# RPI-Lora-Gateway-Shield.net
KiCad netlist of a schematic drawn in EAGLE
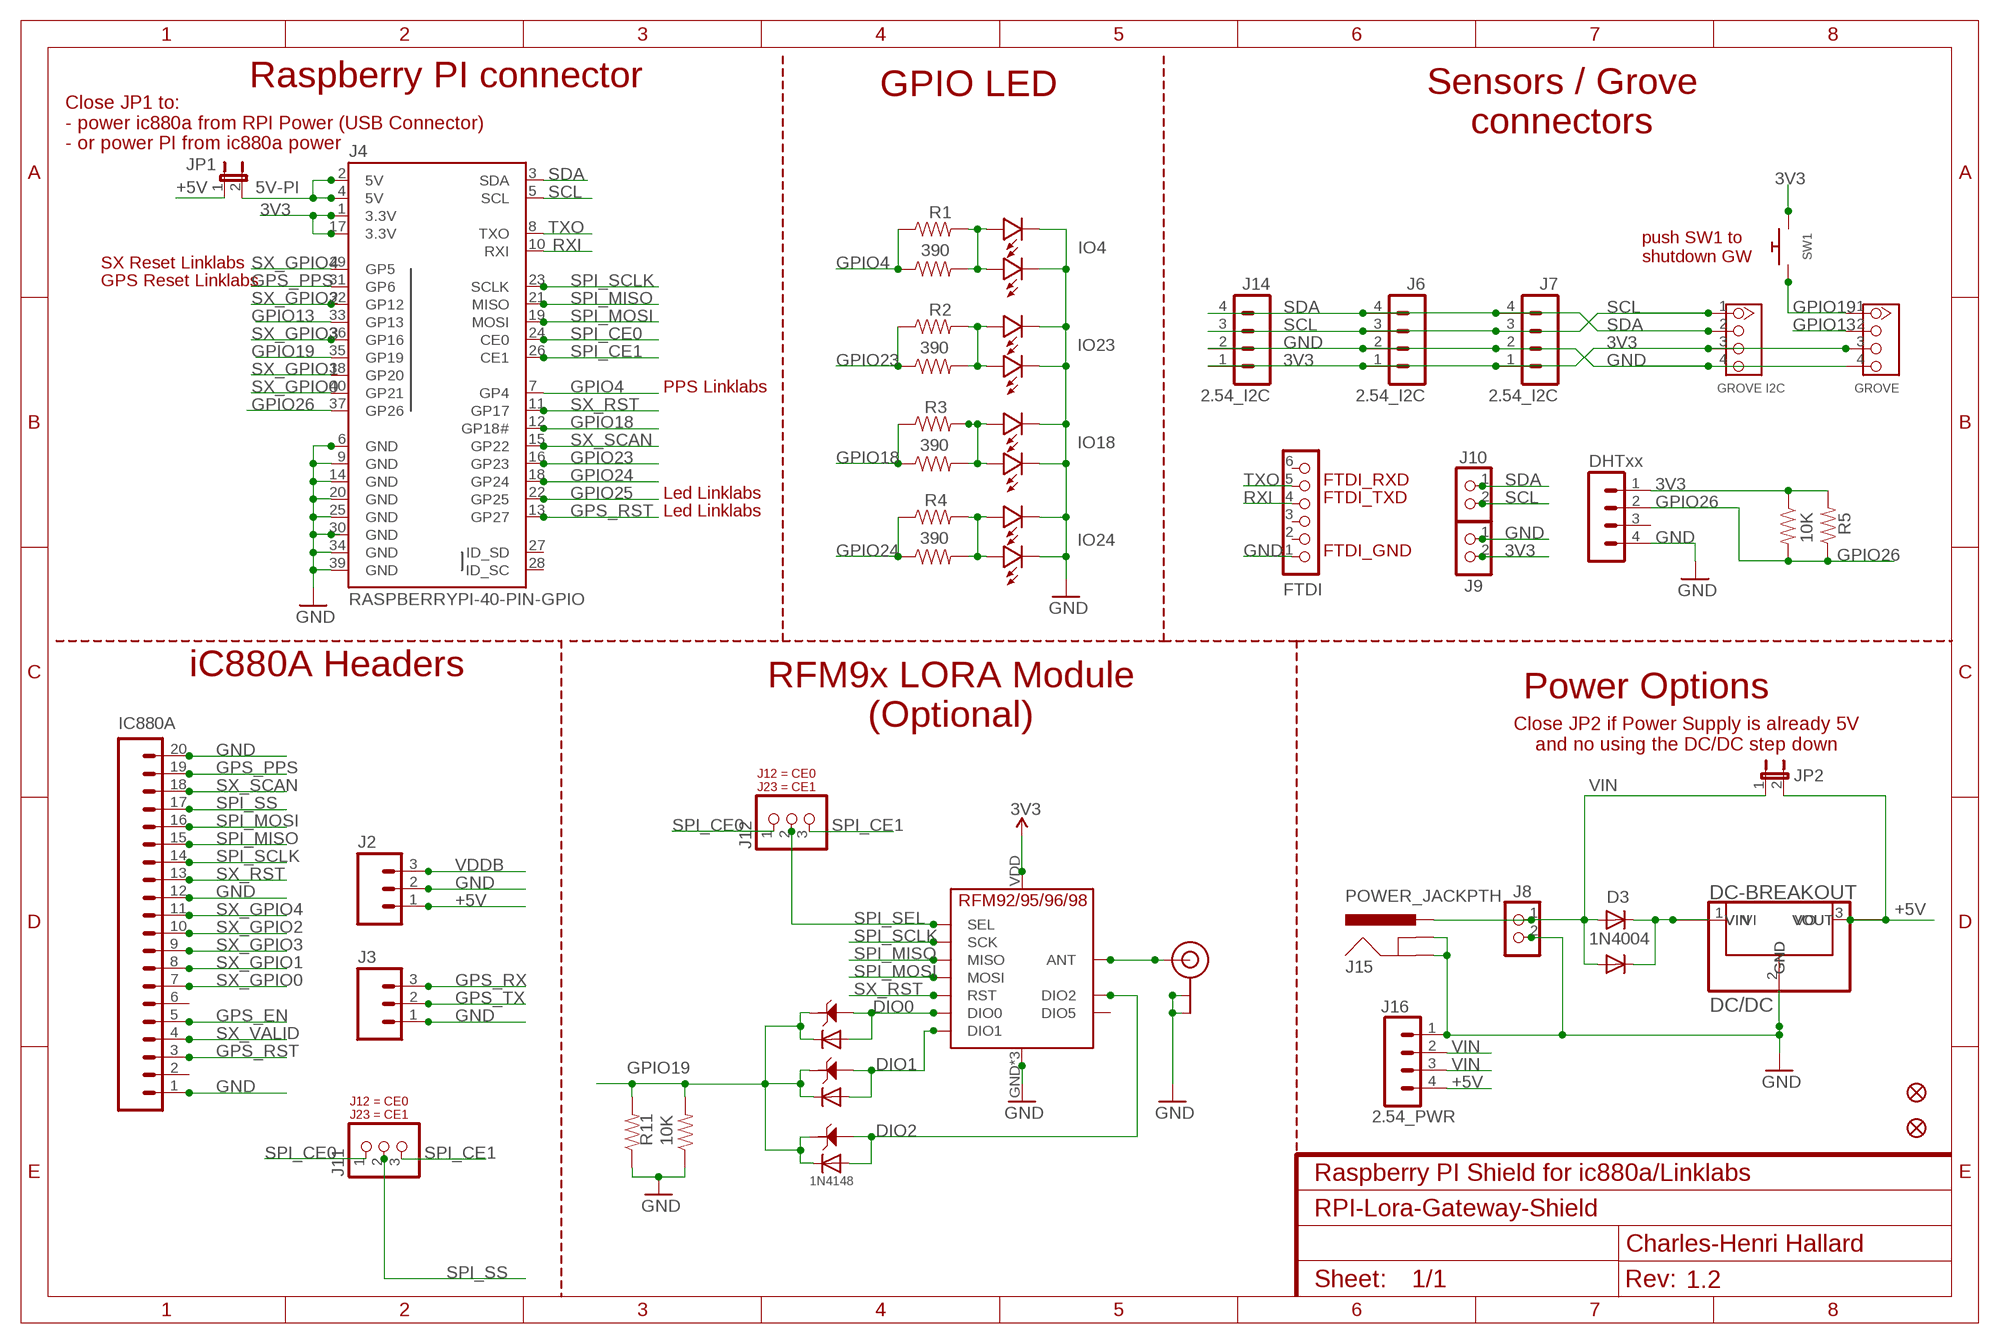
[diagram p0: schematic, sheet 1]

(export (version "E")
  (design (tool "Eeschema 10.0.6"))
  (components
    (comp (ref "D0")
      (value "1N4148")
      (footprint "eagle-import:SOD123-2.7X1.6")
      (libsource (lib "eagle-import") (part "D-ESD-2P-CESD5V0D1"))
    )
    (comp (ref "D1")
      (value "1N4148")
      (footprint "eagle-import:SOD123-2.7X1.6")
      (libsource (lib "eagle-import") (part "D-ESD-2P-CESD5V0D1"))
    )
    (comp (ref "D2")
      (value "1N4148")
      (footprint "eagle-import:SOD123-2.7X1.6")
      (libsource (lib "eagle-import") (part "D-ESD-2P-CESD5V0D1"))
    )
    (comp (ref "D3")
      (value "1N4004")
      (footprint "eagle-import:DO41-10")
      (libsource (lib "eagle-import") (part "1N4004"))
    )
    (comp (ref "D4")
      (value "1N4007")
      (footprint "eagle-import:DO-214AC")
      (libsource (lib "eagle-import") (part "DIODE-DO-214AC"))
    )
    (comp (ref "D5")
      (value "1N4148")
      (footprint "eagle-import:DO-1N4148")
      (libsource (lib "eagle-import") (part "DIODEDO-1N4148"))
    )
    (comp (ref "D6")
      (value "DIODEDO-1N4148")
      (footprint "eagle-import:DO-1N4148")
      (libsource (lib "eagle-import") (part "DIODEDO-1N4148"))
    )
    (comp (ref "D7")
      (value "DIODEDO-1N4148")
      (footprint "eagle-import:DO-1N4148")
      (libsource (lib "eagle-import") (part "DIODEDO-1N4148"))
    )
    (comp (ref "DC/DC")
      (value "DC-BREAKOUT")
      (footprint "eagle-import:DC-BREAKOUT")
      (libsource (lib "eagle-import") (part "DC-BREAKOUTSTD"))
    )
    (comp (ref "FID2")
      (value "FIDUCIAL\"\"")
      (footprint "eagle-import:FIDUCIAL_1MM")
      (libsource (lib "eagle-import") (part "FIDUCIAL{dblquote}{dblquote}"))
    )
    (comp (ref "FID3")
      (value "FIDUCIAL\"\"")
      (footprint "eagle-import:FIDUCIAL_1MM")
      (libsource (lib "eagle-import") (part "FIDUCIAL{dblquote}{dblquote}"))
    )
    (comp (ref "FTDI")
      (value "CON_HEADER_1X06-PTH")
      (footprint "eagle-import:M1X6")
      (libsource (lib "eagle-import") (part "CON_HEADER_1X06-PTH"))
    )
    (comp (ref "IC880A")
      (value "M20LOCK")
      (footprint "eagle-import:1X20_LOCK")
      (libsource (lib "eagle-import") (part "M20LOCK"))
    )
    (comp (ref "J1")
      (value "GROVE")
      (footprint "eagle-import:HW4-2.0")
      (libsource (lib "eagle-import") (part "GROVE-CONNECTOR-DIP(4P-2.0)"))
    )
    (comp (ref "J2")
      (value "M03LOCK")
      (footprint "eagle-import:1X03_LOCK")
      (libsource (lib "eagle-import") (part "M03LOCK"))
    )
    (comp (ref "J3")
      (value "M03LOCK")
      (footprint "eagle-import:1X03_LOCK")
      (libsource (lib "eagle-import") (part "M03LOCK"))
    )
    (comp (ref "J4")
      (value "RASPBERRYPI-40-PIN-GPIO")
      (footprint "eagle-import:2X20-SHROUDED")
      (libsource (lib "eagle-import") (part "RASPBERRYPI-40-PIN-GPIO"))
    )
    (comp (ref "J5")
      (value "DHTxx")
      (footprint "eagle-import:1X04_NO_LOCK")
      (libsource (lib "eagle-import") (part "CON_HEADER_1X04'NO_LOCK'"))
    )
    (comp (ref "J6")
      (value "2.54_I2C")
      (footprint "eagle-import:1X04_NO_LOCK")
      (libsource (lib "eagle-import") (part "CON_HEADER_1X04'NO_LOCK'"))
    )
    (comp (ref "J7")
      (value "2.54_I2C")
      (footprint "eagle-import:1X04_NO_LOCK")
      (libsource (lib "eagle-import") (part "CON_HEADER_1X04'NO_LOCK'"))
    )
    (comp (ref "J8")
      (value "CON_TERMINAL_BLOCK_02-5MM")
      (footprint "eagle-import:TERMINAL_BLOCK_2P_5")
      (libsource (lib "eagle-import") (part "CON_TERMINAL_BLOCK_02-5MM"))
    )
    (comp (ref "J9")
      (value "CON_TERMINAL_BLOCK_02-5MM")
      (footprint "eagle-import:TERMINAL_BLOCK_2P_5")
      (libsource (lib "eagle-import") (part "CON_TERMINAL_BLOCK_02-5MM"))
    )
    (comp (ref "J10")
      (value "CON_TERMINAL_BLOCK_02-5MM")
      (footprint "eagle-import:TERMINAL_BLOCK_2P_5")
      (libsource (lib "eagle-import") (part "CON_TERMINAL_BLOCK_02-5MM"))
    )
    (comp (ref "J11")
      (value "JUMPER_1X30805")
      (footprint "eagle-import:JP3_0805")
      (fields
        (field (name "J12") "optA")
        (field (name "J23") "optB")
        (field (name "J12_1") "CE0")
        (field (name "J23_1") "CE1")
      )
      (libsource (lib "eagle-import") (part "JUMPER_1X30805"))
    )
    (comp (ref "J12")
      (value "JUMPER_1X30805")
      (footprint "eagle-import:JP3_0805")
      (fields
        (field (name "J12") "optA")
        (field (name "J23") "optB")
        (field (name "J12_1") "CE0")
        (field (name "J23_1") "CE1")
      )
      (libsource (lib "eagle-import") (part "JUMPER_1X30805"))
    )
    (comp (ref "J13")
      (value "GROVE I2C")
      (footprint "eagle-import:HW4-2.0")
      (libsource (lib "eagle-import") (part "GROVE-CONNECTOR-DIP(4P-2.0)"))
    )
    (comp (ref "J14")
      (value "2.54_I2C")
      (footprint "eagle-import:1X04_NO_LOCK")
      (libsource (lib "eagle-import") (part "CON_HEADER_1X04'NO_LOCK'"))
    )
    (comp (ref "J15")
      (value "POWER_JACKPTH")
      (footprint "eagle-import:POWER_JACK_PTH")
      (libsource (lib "eagle-import") (part "POWER_JACKPTH"))
    )
    (comp (ref "J16")
      (value "2.54_PWR")
      (footprint "eagle-import:1X04_NO_LOCK")
      (libsource (lib "eagle-import") (part "CON_HEADER_1X04'NO_LOCK'"))
    )
    (comp (ref "JP1")
      (value "JUMPER2")
      (footprint "eagle-import:JUMPER2")
      (libsource (lib "eagle-import") (part "JUMPER2"))
    )
    (comp (ref "JP2")
      (value "JUMPER2")
      (footprint "eagle-import:JUMPER2")
      (libsource (lib "eagle-import") (part "JUMPER2"))
    )
    (comp (ref "LED1")
      (value "LED0805")
      (footprint "eagle-import:0805-LED")
      (libsource (lib "eagle-import") (part "LED0805"))
    )
    (comp (ref "LED2")
      (value "LED0805")
      (footprint "eagle-import:0805-LED")
      (libsource (lib "eagle-import") (part "LED0805"))
    )
    (comp (ref "LED3")
      (value "LED0805")
      (footprint "eagle-import:0805-LED")
      (libsource (lib "eagle-import") (part "LED0805"))
    )
    (comp (ref "LED4")
      (value "LED0805")
      (footprint "eagle-import:0805-LED")
      (libsource (lib "eagle-import") (part "LED0805"))
    )
    (comp (ref "R1")
      (value "390")
      (footprint "eagle-import:AXIAL-0.4")
      (libsource (lib "eagle-import") (part "RESISTORPTH-1/4W"))
    )
    (comp (ref "R2")
      (value "390")
      (footprint "eagle-import:AXIAL-0.4")
      (libsource (lib "eagle-import") (part "RESISTORPTH-1/4W"))
    )
    (comp (ref "R3")
      (value "390")
      (footprint "eagle-import:AXIAL-0.4")
      (libsource (lib "eagle-import") (part "RESISTORPTH-1/4W"))
    )
    (comp (ref "R4")
      (value "390")
      (footprint "eagle-import:AXIAL-0.4")
      (libsource (lib "eagle-import") (part "RESISTORPTH-1/4W"))
    )
    (comp (ref "R5")
      (value "10K")
      (footprint "eagle-import:AXIAL-0.4")
      (libsource (lib "eagle-import") (part "RESISTORPTH-1/4W"))
    )
    (comp (ref "R6")
      (value "RESISTOR0805-RES")
      (footprint "eagle-import:0805-RES")
      (libsource (lib "eagle-import") (part "RESISTOR0805-RES"))
    )
    (comp (ref "R7")
      (value "RESISTOR0805-RES")
      (footprint "eagle-import:0805-RES")
      (libsource (lib "eagle-import") (part "RESISTOR0805-RES"))
    )
    (comp (ref "R8")
      (value "RESISTOR0805-RES")
      (footprint "eagle-import:0805-RES")
      (libsource (lib "eagle-import") (part "RESISTOR0805-RES"))
    )
    (comp (ref "R9")
      (value "RESISTOR0805-RES")
      (footprint "eagle-import:0805-RES")
      (libsource (lib "eagle-import") (part "RESISTOR0805-RES"))
    )
    (comp (ref "R10")
      (value "RESISTOR0805-RES")
      (footprint "eagle-import:0805-RES")
      (libsource (lib "eagle-import") (part "RESISTOR0805-RES"))
    )
    (comp (ref "R11")
      (value "10K")
      (footprint "eagle-import:AXIAL-0.4")
      (libsource (lib "eagle-import") (part "RESISTORPTH-1/4W"))
    )
    (comp (ref "R12")
      (value "RESISTOR0805-RES")
      (footprint "eagle-import:0805-RES")
      (libsource (lib "eagle-import") (part "RESISTOR0805-RES"))
    )
    (comp (ref "SW1")
      (value "SWITCH_PUSHBUTTONEVQ-PE")
      (footprint "eagle-import:TACT_PANA-EVQ")
      (libsource (lib "eagle-import") (part "SWITCH_PUSHBUTTONEVQ-PE"))
    )
    (comp (ref "U$2")
      (value "RFM95")
      (footprint "eagle-import:RFM95")
      (libsource (lib "eagle-import") (part "RFM95"))
    )
    (comp (ref "U$3")
      (value "ANTENNA-UFL")
      (footprint "eagle-import:UFL_PAD")
      (libsource (lib "eagle-import") (part "ANTENNA-UFL"))
    )
    (comp (ref "U$4")
      (value "IO4")
      (footprint "eagle-import:LED3MM")
      (libsource (lib "eagle-import") (part "LED3MM"))
    )
    (comp (ref "U$5")
      (value "IO23")
      (footprint "eagle-import:LED3MM")
      (libsource (lib "eagle-import") (part "LED3MM"))
    )
    (comp (ref "U$6")
      (value "IO18")
      (footprint "eagle-import:LED3MM")
      (libsource (lib "eagle-import") (part "LED3MM"))
    )
    (comp (ref "U$7")
      (value "IO24")
      (footprint "eagle-import:LED3MM")
      (libsource (lib "eagle-import") (part "LED3MM"))
    )
    (comp (ref "U$8")
      (value "DC-BREAKOUTFIXED")
      (footprint "eagle-import:DC-DC-FIXED")
      (libsource (lib "eagle-import") (part "DC-BREAKOUTFIXED"))
    )
    (comp (ref "U$11")
      (value "OKI-78SR")
      (footprint "eagle-import:OKI-78SRH")
      (libsource (lib "eagle-import") (part "DCDC_OKI-78SRHORZ"))
    )
  )
  (nets
    (net (code "1") (name "/+5V") (class "Default")
      (node (ref "DC/DC") (pin "VOUT-1") (pinfunction "VOUT_VOUT-1") (pintype "output"))
      (node (ref "DC/DC") (pin "VOUT-2") (pinfunction "VOUT_VOUT-2") (pintype "output"))
      (node (ref "J16") (pin "4") (pinfunction "4_4") (pintype "passive"))
      (node (ref "J2") (pin "1") (pinfunction "1_1") (pintype "passive"))
      (node (ref "JP1") (pin "1") (pinfunction "1_1") (pintype "passive"))
      (node (ref "JP2") (pin "2") (pinfunction "2_2") (pintype "passive"))
      (node (ref "U$11") (pin "3") (pinfunction "VO_3") (pintype "bidirectional"))
      (node (ref "U$8") (pin "VOUT-1") (pinfunction "VOUT_VOUT-1") (pintype "output"))
      (node (ref "U$8") (pin "VOUT-2") (pinfunction "VOUT_VOUT-2") (pintype "output"))
    )
    (net (code "2") (name "/5V-PI") (class "Default")
      (node (ref "J4") (pin "2") (pinfunction "5V_2") (pintype "power_in"))
      (node (ref "J4") (pin "4") (pinfunction "5V_4") (pintype "power_in"))
      (node (ref "JP1") (pin "2") (pinfunction "2_2") (pintype "passive"))
    )
    (net (code "3") (name "/DIO0") (class "Default")
      (node (ref "D0") (pin "1") (pinfunction "1_1") (pintype "bidirectional"))
      (node (ref "D6") (pin "A") (pinfunction "A_A") (pintype "passive"))
      (node (ref "U$2") (pin "DIO0") (pinfunction "DIO0_DIO0") (pintype "open_collector"))
    )
    (net (code "4") (name "/DIO1") (class "Default")
      (node (ref "D1") (pin "1") (pinfunction "1_1") (pintype "bidirectional"))
      (node (ref "D7") (pin "A") (pinfunction "A_A") (pintype "passive"))
      (node (ref "U$2") (pin "DIO1") (pinfunction "DIO1_DIO1") (pintype "open_collector"))
    )
    (net (code "5") (name "/DIO2") (class "Default")
      (node (ref "D2") (pin "1") (pinfunction "1_1") (pintype "bidirectional"))
      (node (ref "D5") (pin "A") (pinfunction "A_A") (pintype "passive"))
      (node (ref "U$2") (pin "DIO2") (pinfunction "DIO2_DIO2") (pintype "open_collector"))
    )
    (net (code "6") (name "/GPIO4") (class "Default")
      (node (ref "J4") (pin "7") (pinfunction "GP4_7") (pintype "bidirectional"))
      (node (ref "R1") (pin "P$1") (pinfunction "1_P$1") (pintype "passive"))
      (node (ref "R6") (pin "1") (pinfunction "1_1") (pintype "passive"))
    )
    (net (code "7") (name "/GPIO13") (class "Default")
      (node (ref "J1") (pin "2") (pinfunction "2_2") (pintype "bidirectional"))
      (node (ref "J4") (pin "33") (pinfunction "GP13_33") (pintype "bidirectional"))
    )
    (net (code "8") (name "/GPIO18") (class "Default")
      (node (ref "J4") (pin "12") (pinfunction "GP18#_12") (pintype "bidirectional"))
      (node (ref "R3") (pin "P$1") (pinfunction "1_P$1") (pintype "passive"))
      (node (ref "R8") (pin "1") (pinfunction "1_1") (pintype "passive"))
    )
    (net (code "9") (name "/GPIO19") (class "Default")
      (node (ref "D0") (pin "2") (pinfunction "2_2") (pintype "bidirectional"))
      (node (ref "D1") (pin "2") (pinfunction "2_2") (pintype "bidirectional"))
      (node (ref "D2") (pin "2") (pinfunction "2_2") (pintype "bidirectional"))
      (node (ref "D5") (pin "C") (pinfunction "C_C") (pintype "passive"))
      (node (ref "D6") (pin "C") (pinfunction "C_C") (pintype "passive"))
      (node (ref "D7") (pin "C") (pinfunction "C_C") (pintype "passive"))
      (node (ref "J1") (pin "1") (pinfunction "1_1") (pintype "bidirectional"))
      (node (ref "J4") (pin "35") (pinfunction "GP19_35") (pintype "bidirectional"))
      (node (ref "R11") (pin "P$2") (pinfunction "2_P$2") (pintype "passive"))
      (node (ref "R12") (pin "2") (pinfunction "2_2") (pintype "passive"))
      (node (ref "SW1") (pin "P$1") (pinfunction "P$1_P$1") (pintype "passive"))
    )
    (net (code "10") (name "/GPIO23") (class "Default")
      (node (ref "J4") (pin "16") (pinfunction "GP23_16") (pintype "bidirectional"))
      (node (ref "R2") (pin "P$1") (pinfunction "1_P$1") (pintype "passive"))
      (node (ref "R7") (pin "1") (pinfunction "1_1") (pintype "passive"))
    )
    (net (code "11") (name "/GPIO24") (class "Default")
      (node (ref "J4") (pin "18") (pinfunction "GP24_18") (pintype "bidirectional"))
      (node (ref "R4") (pin "P$1") (pinfunction "1_P$1") (pintype "passive"))
      (node (ref "R9") (pin "1") (pinfunction "1_1") (pintype "passive"))
    )
    (net (code "12") (name "/GPIO25") (class "Default")
      (node (ref "J4") (pin "22") (pinfunction "GP25_22") (pintype "bidirectional"))
    )
    (net (code "13") (name "/GPIO26") (class "Default")
      (node (ref "J4") (pin "37") (pinfunction "GP26_37") (pintype "bidirectional"))
      (node (ref "J5") (pin "2") (pinfunction "2_2") (pintype "passive"))
      (node (ref "R10") (pin "1") (pinfunction "1_1") (pintype "passive"))
      (node (ref "R5") (pin "P$2") (pinfunction "2_P$2") (pintype "passive"))
    )
    (net (code "14") (name "/GPS_EN") (class "Default")
      (node (ref "IC880A") (pin "5") (pinfunction "5_5") (pintype "passive"))
    )
    (net (code "15") (name "/GPS_PPS") (class "Default")
      (node (ref "IC880A") (pin "19") (pinfunction "19_19") (pintype "passive"))
      (node (ref "J4") (pin "31") (pinfunction "GP6_31") (pintype "bidirectional"))
    )
    (net (code "16") (name "/GPS_RST") (class "Default")
      (node (ref "IC880A") (pin "3") (pinfunction "3_3") (pintype "passive"))
      (node (ref "J4") (pin "13") (pinfunction "GP27_13") (pintype "bidirectional"))
    )
    (net (code "17") (name "/GPS_RX") (class "Default")
      (node (ref "J3") (pin "3") (pinfunction "3_3") (pintype "passive"))
    )
    (net (code "18") (name "/GPS_TX") (class "Default")
      (node (ref "J3") (pin "2") (pinfunction "2_2") (pintype "passive"))
    )
    (net (code "19") (name "/RXI") (class "Default")
      (node (ref "FTDI") (pin "4") (pinfunction "4_4") (pintype "passive"))
      (node (ref "J4") (pin "10") (pinfunction "RXI_10") (pintype "input"))
    )
    (net (code "20") (name "/SCL") (class "Default")
      (node (ref "J10") (pin "2") (pinfunction "2_2") (pintype "passive"))
      (node (ref "J13") (pin "1") (pinfunction "1_1") (pintype "bidirectional"))
      (node (ref "J14") (pin "3") (pinfunction "3_3") (pintype "passive"))
      (node (ref "J4") (pin "5") (pinfunction "SCL_5") (pintype "bidirectional"))
      (node (ref "J6") (pin "3") (pinfunction "3_3") (pintype "passive"))
      (node (ref "J7") (pin "3") (pinfunction "3_3") (pintype "passive"))
    )
    (net (code "21") (name "/SDA") (class "Default")
      (node (ref "J10") (pin "1") (pinfunction "1_1") (pintype "passive"))
      (node (ref "J13") (pin "2") (pinfunction "2_2") (pintype "bidirectional"))
      (node (ref "J14") (pin "4") (pinfunction "4_4") (pintype "passive"))
      (node (ref "J4") (pin "3") (pinfunction "SDA_3") (pintype "bidirectional"))
      (node (ref "J6") (pin "4") (pinfunction "4_4") (pintype "passive"))
      (node (ref "J7") (pin "4") (pinfunction "4_4") (pintype "passive"))
    )
    (net (code "22") (name "/SPI_CE0") (class "Default")
      (node (ref "J11") (pin "1") (pinfunction "1_1") (pintype "passive"))
      (node (ref "J12") (pin "1") (pinfunction "1_1") (pintype "passive"))
      (node (ref "J4") (pin "24") (pinfunction "CE0_24") (pintype "output"))
    )
    (net (code "23") (name "/SPI_CE1") (class "Default")
      (node (ref "J11") (pin "3") (pinfunction "3_3") (pintype "passive"))
      (node (ref "J12") (pin "3") (pinfunction "3_3") (pintype "passive"))
      (node (ref "J4") (pin "26") (pinfunction "CE1_26") (pintype "output"))
    )
    (net (code "24") (name "/SPI_MISO") (class "Default")
      (node (ref "IC880A") (pin "15") (pinfunction "15_15") (pintype "passive"))
      (node (ref "J4") (pin "21") (pinfunction "MISO_21") (pintype "input"))
      (node (ref "U$2") (pin "MISO") (pinfunction "MISO_MISO") (pintype "input"))
    )
    (net (code "25") (name "/SPI_MOSI") (class "Default")
      (node (ref "IC880A") (pin "16") (pinfunction "16_16") (pintype "passive"))
      (node (ref "J4") (pin "19") (pinfunction "MOSI_19") (pintype "output"))
      (node (ref "U$2") (pin "MOSI") (pinfunction "MOSI_MOSI") (pintype "output"))
    )
    (net (code "26") (name "/SPI_SCLK") (class "Default")
      (node (ref "IC880A") (pin "14") (pinfunction "14_14") (pintype "passive"))
      (node (ref "J4") (pin "23") (pinfunction "SCLK_23") (pintype "output"))
      (node (ref "U$2") (pin "SCK") (pinfunction "SCK_SCK") (pintype "input"))
    )
    (net (code "27") (name "/SPI_SEL") (class "Default")
      (node (ref "J12") (pin "2") (pinfunction "2_2") (pintype "passive"))
      (node (ref "U$2") (pin "NSS") (pinfunction "SEL_NSS") (pintype "input"))
    )
    (net (code "28") (name "/SPI_SS") (class "Default")
      (node (ref "IC880A") (pin "17") (pinfunction "17_17") (pintype "passive"))
      (node (ref "J11") (pin "2") (pinfunction "2_2") (pintype "passive"))
    )
    (net (code "29") (name "/SX_GPIO0") (class "Default")
      (node (ref "IC880A") (pin "7") (pinfunction "7_7") (pintype "passive"))
      (node (ref "J4") (pin "40") (pinfunction "GP21_40") (pintype "bidirectional"))
    )
    (net (code "30") (name "/SX_GPIO1") (class "Default")
      (node (ref "IC880A") (pin "8") (pinfunction "8_8") (pintype "passive"))
      (node (ref "J4") (pin "38") (pinfunction "GP20_38") (pintype "bidirectional"))
    )
    (net (code "31") (name "/SX_GPIO2") (class "Default")
      (node (ref "IC880A") (pin "10") (pinfunction "10_10") (pintype "passive"))
      (node (ref "J4") (pin "32") (pinfunction "GP12_32") (pintype "bidirectional"))
    )
    (net (code "32") (name "/SX_GPIO3") (class "Default")
      (node (ref "IC880A") (pin "9") (pinfunction "9_9") (pintype "passive"))
      (node (ref "J4") (pin "36") (pinfunction "GP16_36") (pintype "bidirectional"))
    )
    (net (code "33") (name "/SX_GPIO4") (class "Default")
      (node (ref "IC880A") (pin "11") (pinfunction "11_11") (pintype "passive"))
      (node (ref "J4") (pin "29") (pinfunction "GP5_29") (pintype "bidirectional"))
    )
    (net (code "34") (name "/SX_RST") (class "Default")
      (node (ref "IC880A") (pin "13") (pinfunction "13_13") (pintype "passive"))
      (node (ref "J4") (pin "11") (pinfunction "GP17_11") (pintype "bidirectional"))
      (node (ref "U$2") (pin "RST") (pinfunction "RST_RST") (pintype "open_collector"))
    )
    (net (code "35") (name "/SX_SCAN") (class "Default")
      (node (ref "IC880A") (pin "18") (pinfunction "18_18") (pintype "passive"))
      (node (ref "J4") (pin "15") (pinfunction "GP22_15") (pintype "bidirectional"))
    )
    (net (code "36") (name "/SX_VALID") (class "Default")
      (node (ref "IC880A") (pin "4") (pinfunction "4_4") (pintype "passive"))
    )
    (net (code "37") (name "/TXO") (class "Default")
      (node (ref "FTDI") (pin "5") (pinfunction "5_5") (pintype "passive"))
      (node (ref "J4") (pin "8") (pinfunction "TXO_8") (pintype "output"))
    )
    (net (code "38") (name "/VDDB") (class "Default")
      (node (ref "J2") (pin "3") (pinfunction "3_3") (pintype "passive"))
    )
    (net (code "39") (name "/VIN") (class "Default")
      (node (ref "D3") (pin "A") (pinfunction "A_A") (pintype "passive"))
      (node (ref "D4") (pin "2") (pinfunction "A_2") (pintype "passive"))
      (node (ref "J15") (pin "PWR") (pinfunction "PWR_PWR") (pintype "bidirectional"))
      (node (ref "J16") (pin "2") (pinfunction "2_2") (pintype "passive"))
      (node (ref "J16") (pin "3") (pinfunction "3_3") (pintype "passive"))
      (node (ref "J8") (pin "1") (pinfunction "1_1") (pintype "passive"))
      (node (ref "JP2") (pin "1") (pinfunction "1_1") (pintype "passive"))
    )
    (net (code "40") (name "3V3") (class "Default")
      (node (ref "J1") (pin "3") (pinfunction "3_3") (pintype "bidirectional"))
      (node (ref "J13") (pin "3") (pinfunction "3_3") (pintype "bidirectional"))
      (node (ref "J14") (pin "1") (pinfunction "1_1") (pintype "passive"))
      (node (ref "J4") (pin "1") (pinfunction "3.3V_1") (pintype "power_in"))
      (node (ref "J4") (pin "17") (pinfunction "3.3V_17") (pintype "power_in"))
      (node (ref "J5") (pin "1") (pinfunction "1_1") (pintype "passive"))
      (node (ref "J6") (pin "1") (pinfunction "1_1") (pintype "passive"))
      (node (ref "J7") (pin "1") (pinfunction "1_1") (pintype "passive"))
      (node (ref "J9") (pin "2") (pinfunction "2_2") (pintype "passive"))
      (node (ref "R10") (pin "2") (pinfunction "2_2") (pintype "passive"))
      (node (ref "R5") (pin "P$1") (pinfunction "1_P$1") (pintype "passive"))
      (node (ref "SW1") (pin "P$2") (pinfunction "P$2_P$2") (pintype "passive"))
      (node (ref "U$2") (pin "VDD") (pinfunction "VCC_VDD") (pintype "power_in"))
    )
    (net (code "41") (name "GND") (class "Default")
      (node (ref "DC/DC") (pin "GND-1") (pinfunction "GND_GND-1") (pintype "passive"))
      (node (ref "DC/DC") (pin "GND-2") (pinfunction "GND_GND-2") (pintype "passive"))
      (node (ref "DC/DC") (pin "GND-3") (pinfunction "GND_GND-3") (pintype "passive"))
      (node (ref "DC/DC") (pin "GND-4") (pinfunction "GND_GND-4") (pintype "passive"))
      (node (ref "FTDI") (pin "1") (pinfunction "1_1") (pintype "bidirectional"))
      (node (ref "IC880A") (pin "1") (pinfunction "1_1") (pintype "passive"))
      (node (ref "IC880A") (pin "12") (pinfunction "12_12") (pintype "passive"))
      (node (ref "IC880A") (pin "20") (pinfunction "20_20") (pintype "passive"))
      (node (ref "J1") (pin "4") (pinfunction "4_4") (pintype "bidirectional"))
      (node (ref "J13") (pin "4") (pinfunction "4_4") (pintype "bidirectional"))
      (node (ref "J14") (pin "2") (pinfunction "2_2") (pintype "passive"))
      (node (ref "J15") (pin "GND") (pinfunction "GND_GND") (pintype "bidirectional"))
      (node (ref "J15") (pin "GNDBREAK") (pinfunction "GNDBREAK_GNDBREAK") (pintype "bidirectional"))
      (node (ref "J16") (pin "1") (pinfunction "1_1") (pintype "passive"))
      (node (ref "J2") (pin "2") (pinfunction "2_2") (pintype "passive"))
      (node (ref "J3") (pin "1") (pinfunction "1_1") (pintype "passive"))
      (node (ref "J4") (pin "14") (pinfunction "GND_14") (pintype "power_in"))
      (node (ref "J4") (pin "20") (pinfunction "GND_20") (pintype "power_in"))
      (node (ref "J4") (pin "25") (pinfunction "GND_25") (pintype "power_in"))
      (node (ref "J4") (pin "30") (pinfunction "GND_30") (pintype "power_in"))
      (node (ref "J4") (pin "34") (pinfunction "GND_34") (pintype "power_in"))
      (node (ref "J4") (pin "39") (pinfunction "GND_39") (pintype "power_in"))
      (node (ref "J4") (pin "6") (pinfunction "GND_6") (pintype "power_in"))
      (node (ref "J4") (pin "9") (pinfunction "GND_9") (pintype "power_in"))
      (node (ref "J5") (pin "4") (pinfunction "4_4") (pintype "passive"))
      (node (ref "J6") (pin "2") (pinfunction "2_2") (pintype "passive"))
      (node (ref "J7") (pin "2") (pinfunction "2_2") (pintype "passive"))
      (node (ref "J8") (pin "2") (pinfunction "2_2") (pintype "passive"))
      (node (ref "J9") (pin "1") (pinfunction "1_1") (pintype "passive"))
      (node (ref "LED1") (pin "MINUS") (pinfunction "MINUS_MINUS") (pintype "passive"))
      (node (ref "LED2") (pin "MINUS") (pinfunction "MINUS_MINUS") (pintype "passive"))
      (node (ref "LED3") (pin "MINUS") (pinfunction "MINUS_MINUS") (pintype "passive"))
      (node (ref "LED4") (pin "MINUS") (pinfunction "MINUS_MINUS") (pintype "passive"))
      (node (ref "R11") (pin "P$1") (pinfunction "1_P$1") (pintype "passive"))
      (node (ref "R12") (pin "1") (pinfunction "1_1") (pintype "passive"))
      (node (ref "U$11") (pin "2") (pinfunction "GND_2") (pintype "bidirectional"))
      (node (ref "U$2") (pin "GND") (pinfunction "GND_GND") (pintype "power_in"))
      (node (ref "U$2") (pin "GND1") (pinfunction "GND_GND1") (pintype "power_in"))
      (node (ref "U$2") (pin "GND2") (pinfunction "GND_GND2") (pintype "power_in"))
      (node (ref "U$3") (pin "GND1") (pinfunction "GND_GND1") (pintype "bidirectional"))
      (node (ref "U$3") (pin "GND2") (pinfunction "GND_GND2") (pintype "bidirectional"))
      (node (ref "U$4") (pin "MINUS") (pinfunction "MINUS_MINUS") (pintype "passive"))
      (node (ref "U$5") (pin "MINUS") (pinfunction "MINUS_MINUS") (pintype "passive"))
      (node (ref "U$6") (pin "MINUS") (pinfunction "MINUS_MINUS") (pintype "passive"))
      (node (ref "U$7") (pin "MINUS") (pinfunction "MINUS_MINUS") (pintype "passive"))
      (node (ref "U$8") (pin "GND-1") (pinfunction "GND_GND-1") (pintype "passive"))
      (node (ref "U$8") (pin "GND-2") (pinfunction "GND_GND-2") (pintype "passive"))
      (node (ref "U$8") (pin "GND-3") (pinfunction "GND_GND-3") (pintype "passive"))
      (node (ref "U$8") (pin "GND-4") (pinfunction "GND_GND-4") (pintype "passive"))
    )
    (net (code "42") (name "Net-(D4-C)") (class "Default")
      (node (ref "D3") (pin "C") (pinfunction "C_C") (pintype "passive"))
      (node (ref "D4") (pin "1") (pinfunction "C_1") (pintype "passive"))
      (node (ref "DC/DC") (pin "VIN-1") (pinfunction "VIN_VIN-1") (pintype "input"))
      (node (ref "DC/DC") (pin "VIN-2") (pinfunction "VIN_VIN-2") (pintype "input"))
      (node (ref "U$11") (pin "1") (pinfunction "VI_1") (pintype "bidirectional"))
      (node (ref "U$8") (pin "VIN-1") (pinfunction "VIN_VIN-1") (pintype "input"))
      (node (ref "U$8") (pin "VIN-2") (pinfunction "VIN_VIN-2") (pintype "input"))
    )
    (net (code "43") (name "Net-(R1-2)") (class "Default")
      (node (ref "LED1") (pin "PLUS") (pinfunction "PLUS_PLUS") (pintype "passive"))
      (node (ref "R1") (pin "P$2") (pinfunction "2_P$2") (pintype "passive"))
      (node (ref "R6") (pin "2") (pinfunction "2_2") (pintype "passive"))
      (node (ref "U$4") (pin "PLUS") (pinfunction "PLUS_PLUS") (pintype "passive"))
    )
    (net (code "44") (name "Net-(R2-2)") (class "Default")
      (node (ref "LED2") (pin "PLUS") (pinfunction "PLUS_PLUS") (pintype "passive"))
      (node (ref "R2") (pin "P$2") (pinfunction "2_P$2") (pintype "passive"))
      (node (ref "R7") (pin "2") (pinfunction "2_2") (pintype "passive"))
      (node (ref "U$5") (pin "PLUS") (pinfunction "PLUS_PLUS") (pintype "passive"))
    )
    (net (code "45") (name "Net-(R3-2)") (class "Default")
      (node (ref "LED3") (pin "PLUS") (pinfunction "PLUS_PLUS") (pintype "passive"))
      (node (ref "R3") (pin "P$2") (pinfunction "2_P$2") (pintype "passive"))
      (node (ref "R8") (pin "2") (pinfunction "2_2") (pintype "passive"))
      (node (ref "U$6") (pin "PLUS") (pinfunction "PLUS_PLUS") (pintype "passive"))
    )
    (net (code "46") (name "Net-(R4-2)") (class "Default")
      (node (ref "LED4") (pin "PLUS") (pinfunction "PLUS_PLUS") (pintype "passive"))
      (node (ref "R4") (pin "P$2") (pinfunction "2_P$2") (pintype "passive"))
      (node (ref "R9") (pin "2") (pinfunction "2_2") (pintype "passive"))
      (node (ref "U$7") (pin "PLUS") (pinfunction "PLUS_PLUS") (pintype "passive"))
    )
    (net (code "47") (name "Net-(U$2-PadANT)") (class "Default")
      (node (ref "U$2") (pin "ANT") (pinfunction "ANT_ANT") (pintype "passive"))
      (node (ref "U$3") (pin "ANT1") (pinfunction "SIGNAL_ANT1") (pintype "bidirectional"))
      (node (ref "U$3") (pin "ANT2") (pinfunction "SIGNAL_ANT2") (pintype "bidirectional"))
    )
    (net (code "48") (name "unconnected-(FTDI-Pad2)") (class "Default")
      (node (ref "FTDI") (pin "2") (pinfunction "2_2") (pintype "bidirectional"))
    )
    (net (code "49") (name "unconnected-(FTDI-Pad3)") (class "Default")
      (node (ref "FTDI") (pin "3") (pinfunction "3_3") (pintype "passive"))
    )
    (net (code "50") (name "unconnected-(FTDI-Pad6)") (class "Default")
      (node (ref "FTDI") (pin "6") (pinfunction "6_6") (pintype "passive"))
    )
    (net (code "51") (name "unconnected-(IC880A-Pad2)") (class "Default")
      (node (ref "IC880A") (pin "2") (pinfunction "2_2") (pintype "passive"))
    )
    (net (code "52") (name "unconnected-(IC880A-Pad6)") (class "Default")
      (node (ref "IC880A") (pin "6") (pinfunction "6_6") (pintype "passive"))
    )
    (net (code "53") (name "unconnected-(J4-ID_SC-Pad28)") (class "Default")
      (node (ref "J4") (pin "28") (pinfunction "ID_SC_28") (pintype "bidirectional"))
    )
    (net (code "54") (name "unconnected-(J4-ID_SD-Pad27)") (class "Default")
      (node (ref "J4") (pin "27") (pinfunction "ID_SD_27") (pintype "bidirectional"))
    )
    (net (code "55") (name "unconnected-(J5-Pad3)") (class "Default")
      (node (ref "J5") (pin "3") (pinfunction "3_3") (pintype "passive"))
    )
    (net (code "56") (name "unconnected-(U$2-PadDIO5)") (class "Default")
      (node (ref "U$2") (pin "DIO5") (pinfunction "DIO5_DIO5") (pintype "open_collector"))
    )
  )
)
